# AudioMega_HaGeHa_DIL_v101.net
KiCad netlist of a schematic drawn in EAGLE
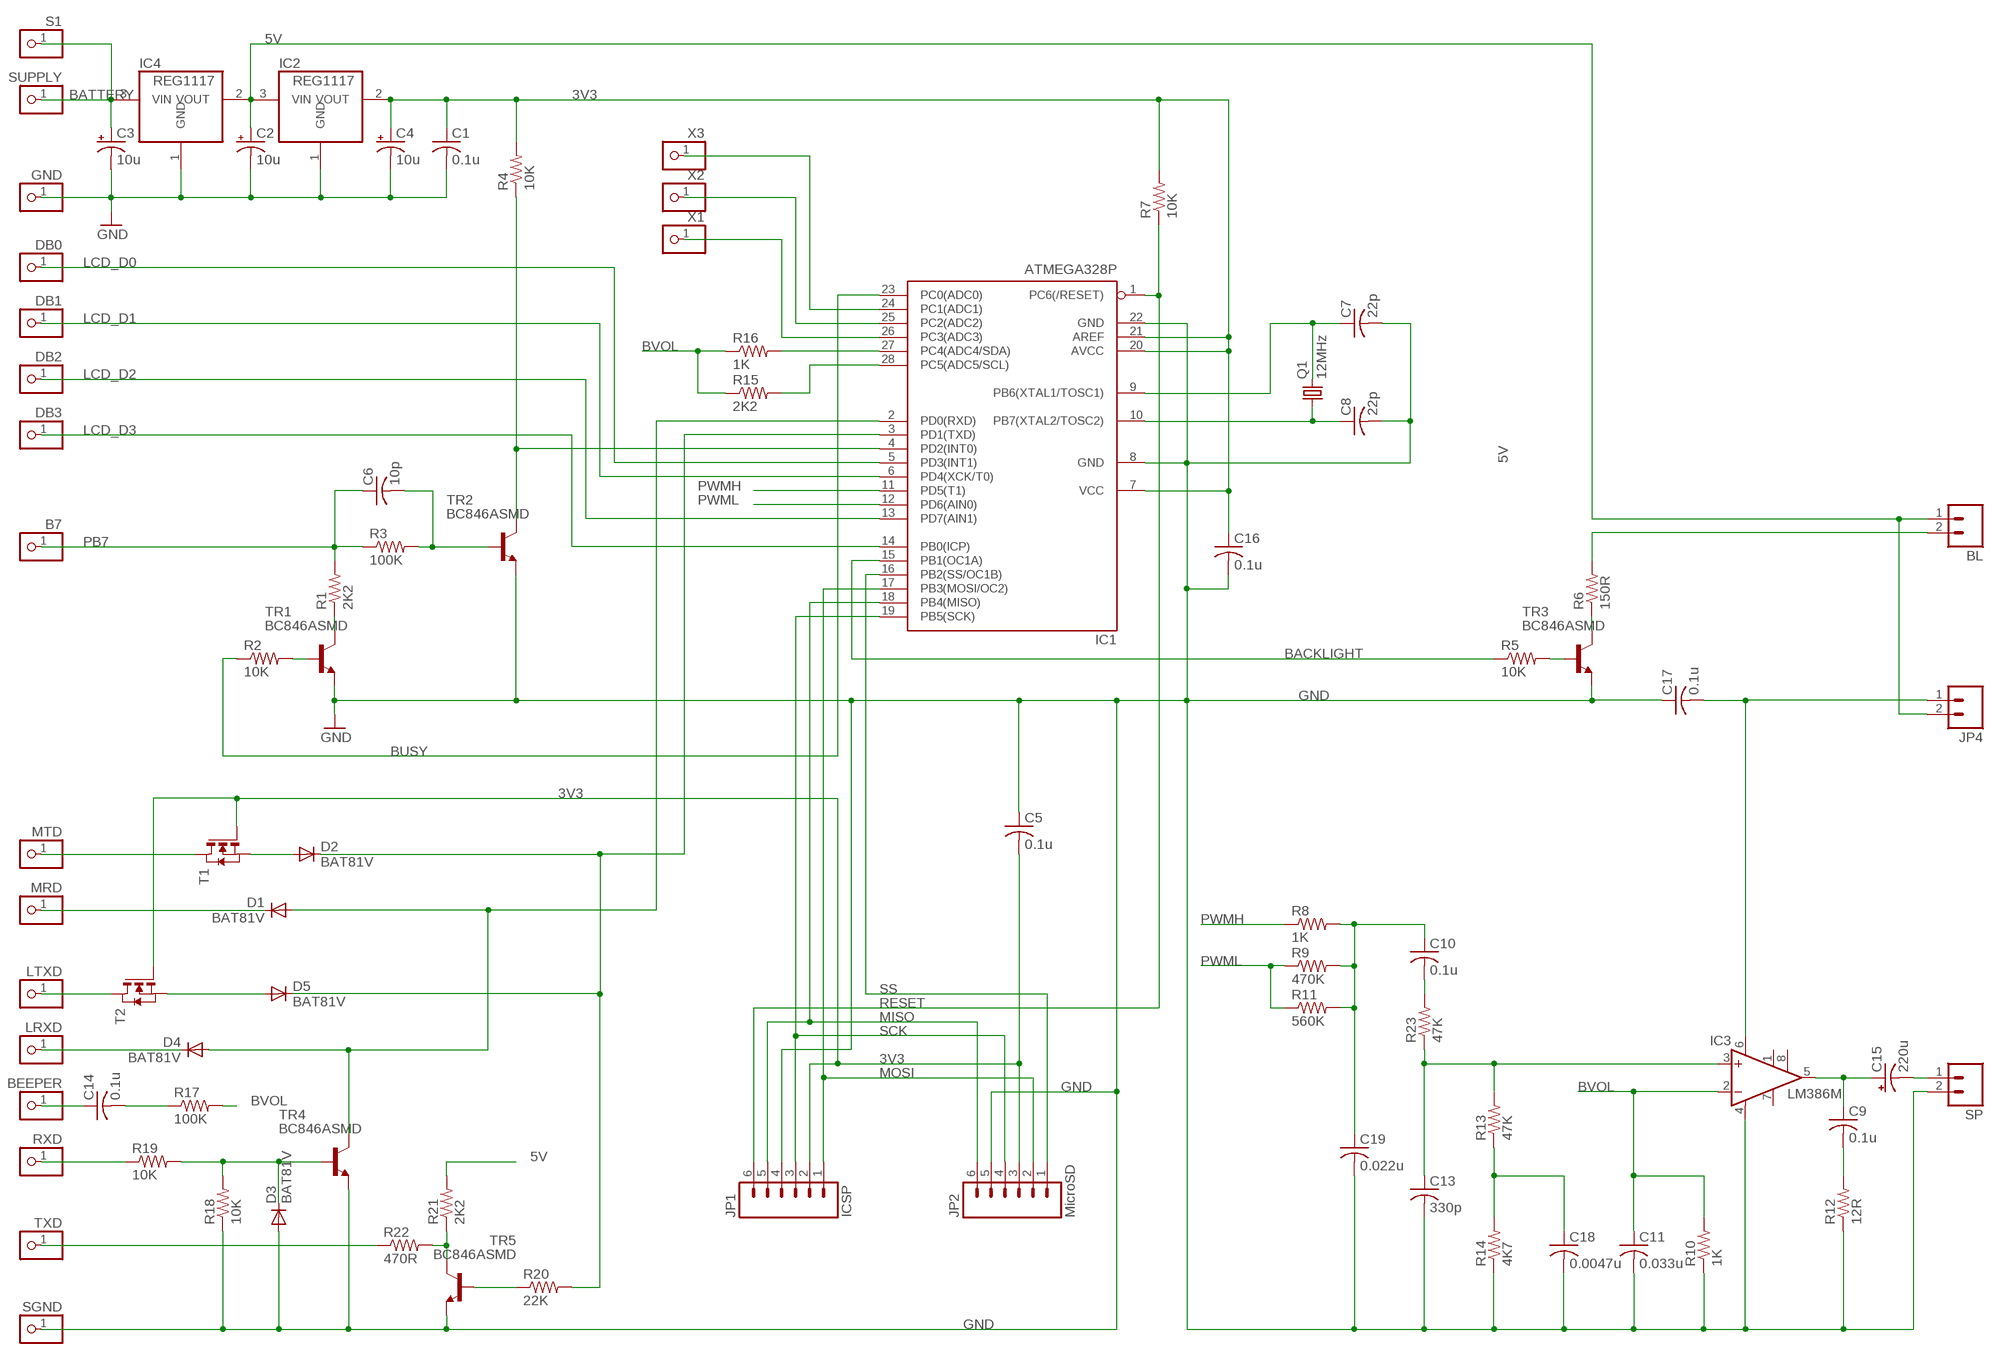
[diagram p0: schematic, sheet 1]

(export (version "E")
  (design (tool "Eeschema 10.0.6"))
  (components
    (comp (ref "B7")
      (value "PINHD-1X1")
      (footprint "eagle-import:1X01")
      (libsource (lib "eagle-import") (part "PINHD-1X1"))
    )
    (comp (ref "BEEPER")
      (value "PINHD-1X1")
      (footprint "eagle-import:1X01")
      (libsource (lib "eagle-import") (part "PINHD-1X1"))
    )
    (comp (ref "BL")
      (value "M02PTH")
      (footprint "eagle-import:1X02")
      (libsource (lib "eagle-import") (part "M02PTH"))
    )
    (comp (ref "C1")
      (value "0.1u")
      (footprint "eagle-import:C1206")
      (libsource (lib "eagle-import") (part "C-USC1206"))
    )
    (comp (ref "C2")
      (value "10u")
      (footprint "eagle-import:A_3216-18R")
      (libsource (lib "eagle-import") (part "CPOL-USA/3216-18R"))
    )
    (comp (ref "C3")
      (value "10u")
      (footprint "eagle-import:A_3216-18R")
      (libsource (lib "eagle-import") (part "CPOL-USA/3216-18R"))
    )
    (comp (ref "C4")
      (value "10u")
      (footprint "eagle-import:A_3216-18R")
      (libsource (lib "eagle-import") (part "CPOL-USA/3216-18R"))
    )
    (comp (ref "C5")
      (value "0.1u")
      (footprint "eagle-import:C1206")
      (libsource (lib "eagle-import") (part "C-USC1206"))
    )
    (comp (ref "C6")
      (value "10p")
      (footprint "eagle-import:C1206")
      (libsource (lib "eagle-import") (part "C-USC1206"))
    )
    (comp (ref "C7")
      (value "22p")
      (footprint "eagle-import:C1206")
      (libsource (lib "eagle-import") (part "C-USC1206"))
    )
    (comp (ref "C8")
      (value "22p")
      (footprint "eagle-import:C1206")
      (libsource (lib "eagle-import") (part "C-USC1206"))
    )
    (comp (ref "C9")
      (value "0.1u")
      (footprint "eagle-import:C1206")
      (libsource (lib "eagle-import") (part "C-USC1206"))
    )
    (comp (ref "C10")
      (value "0.1u")
      (footprint "eagle-import:C1206")
      (libsource (lib "eagle-import") (part "C-USC1206"))
    )
    (comp (ref "C11")
      (value "0.033u")
      (footprint "eagle-import:C1206")
      (libsource (lib "eagle-import") (part "C-USC1206"))
    )
    (comp (ref "C13")
      (value "330p")
      (footprint "eagle-import:C1206")
      (libsource (lib "eagle-import") (part "C-USC1206"))
    )
    (comp (ref "C14")
      (value "0.1u")
      (footprint "eagle-import:C1206")
      (libsource (lib "eagle-import") (part "C-USC1206"))
    )
    (comp (ref "C15")
      (value "220u")
      (footprint "eagle-import:CT7343")
      (libsource (lib "eagle-import") (part "CPOL-USCT7343"))
    )
    (comp (ref "C16")
      (value "0.1u")
      (footprint "eagle-import:C1206")
      (libsource (lib "eagle-import") (part "C-USC1206"))
    )
    (comp (ref "C17")
      (value "0.1u")
      (footprint "eagle-import:C1206")
      (libsource (lib "eagle-import") (part "C-USC1206"))
    )
    (comp (ref "C18")
      (value "0.0047u")
      (footprint "eagle-import:C1206")
      (libsource (lib "eagle-import") (part "C-USC1206"))
    )
    (comp (ref "C19")
      (value "0.022u")
      (footprint "eagle-import:C1206")
      (libsource (lib "eagle-import") (part "C-USC1206"))
    )
    (comp (ref "D1")
      (value "BAT81V")
      (footprint "eagle-import:SOD123")
      (libsource (lib "eagle-import") (part "DIODE-SOD123"))
    )
    (comp (ref "D2")
      (value "BAT81V")
      (footprint "eagle-import:SOD123")
      (libsource (lib "eagle-import") (part "DIODE-SOD123"))
    )
    (comp (ref "D3")
      (value "BAT81V")
      (footprint "eagle-import:SOD123")
      (libsource (lib "eagle-import") (part "DIODE-SOD123"))
    )
    (comp (ref "D4")
      (value "BAT81V")
      (footprint "eagle-import:SOD123")
      (libsource (lib "eagle-import") (part "DIODE-SOD123"))
    )
    (comp (ref "D5")
      (value "BAT81V")
      (footprint "eagle-import:SOD123")
      (libsource (lib "eagle-import") (part "DIODE-SOD123"))
    )
    (comp (ref "DB0")
      (value "PINHD-1X1")
      (footprint "eagle-import:1X01")
      (libsource (lib "eagle-import") (part "PINHD-1X1"))
    )
    (comp (ref "DB1")
      (value "PINHD-1X1")
      (footprint "eagle-import:1X01")
      (libsource (lib "eagle-import") (part "PINHD-1X1"))
    )
    (comp (ref "DB2")
      (value "PINHD-1X1")
      (footprint "eagle-import:1X01")
      (libsource (lib "eagle-import") (part "PINHD-1X1"))
    )
    (comp (ref "DB3")
      (value "PINHD-1X1")
      (footprint "eagle-import:1X01")
      (libsource (lib "eagle-import") (part "PINHD-1X1"))
    )
    (comp (ref "GND")
      (value "PINHD-1X1")
      (footprint "eagle-import:1X01")
      (libsource (lib "eagle-import") (part "PINHD-1X1"))
    )
    (comp (ref "IC1")
      (value "ATMEGA328P")
      (footprint "eagle-import:DIL28-3")
      (fields (field (name "OC_FARNELL") "unknown") (field (name "OC_NEWARK") "unknown"))
      (libsource (lib "eagle-import") (part "MEGA8-P"))
    )
    (comp (ref "IC2")
      (value "REG1117")
      (footprint "eagle-import:SOT223")
      (fields
        (field (name "MPN") "REG1117")
        (field (name "OC_FARNELL") "1097566")
        (field (name "OC_NEWARK") "14P6981")
      )
      (libsource (lib "eagle-import") (part "REG1117"))
    )
    (comp (ref "IC3")
      (value "LM386M")
      (footprint "eagle-import:DIL08")
      (libsource (lib "eagle-import") (part "LM386?-N1"))
    )
    (comp (ref "IC4")
      (value "REG1117")
      (footprint "eagle-import:SOT223")
      (libsource (lib "eagle-import") (part "REG1117"))
    )
    (comp (ref "JP1")
      (value "ICSP")
      (footprint "eagle-import:1X06")
      (libsource (lib "eagle-import") (part "M06SIP"))
    )
    (comp (ref "JP2")
      (value "MicroSD")
      (footprint "eagle-import:1X06")
      (libsource (lib "eagle-import") (part "M06SIP"))
    )
    (comp (ref "JP4")
      (value "M02PTH")
      (footprint "eagle-import:1X02")
      (libsource (lib "eagle-import") (part "M02PTH"))
    )
    (comp (ref "LRXD")
      (value "PINHD-1X1")
      (footprint "eagle-import:1X01")
      (libsource (lib "eagle-import") (part "PINHD-1X1"))
    )
    (comp (ref "LTXD")
      (value "PINHD-1X1")
      (footprint "eagle-import:1X01")
      (libsource (lib "eagle-import") (part "PINHD-1X1"))
    )
    (comp (ref "MRD")
      (value "PINHD-1X1")
      (footprint "eagle-import:1X01")
      (libsource (lib "eagle-import") (part "PINHD-1X1"))
    )
    (comp (ref "MTD")
      (value "PINHD-1X1")
      (footprint "eagle-import:1X01")
      (libsource (lib "eagle-import") (part "PINHD-1X1"))
    )
    (comp (ref "Q1")
      (value "12MHz")
      (footprint "eagle-import:HC49US")
      (libsource (lib "eagle-import") (part "CRYSTALHC49US"))
    )
    (comp (ref "R1")
      (value "2K2")
      (footprint "eagle-import:R1206")
      (libsource (lib "eagle-import") (part "R-US_R1206"))
    )
    (comp (ref "R2")
      (value "10K")
      (footprint "eagle-import:R1206")
      (libsource (lib "eagle-import") (part "R-US_R1206"))
    )
    (comp (ref "R3")
      (value "100K")
      (footprint "eagle-import:R1206")
      (libsource (lib "eagle-import") (part "R-US_R1206"))
    )
    (comp (ref "R4")
      (value "10K")
      (footprint "eagle-import:R1206")
      (libsource (lib "eagle-import") (part "R-US_R1206"))
    )
    (comp (ref "R5")
      (value "10K")
      (footprint "eagle-import:R1206")
      (libsource (lib "eagle-import") (part "R-US_R1206"))
    )
    (comp (ref "R6")
      (value "150R")
      (footprint "eagle-import:R1206")
      (libsource (lib "eagle-import") (part "R-US_R1206"))
    )
    (comp (ref "R7")
      (value "10K")
      (footprint "eagle-import:R1206")
      (libsource (lib "eagle-import") (part "R-US_R1206"))
    )
    (comp (ref "R8")
      (value "1K")
      (footprint "eagle-import:R1206")
      (libsource (lib "eagle-import") (part "R-US_R1206"))
    )
    (comp (ref "R9")
      (value "470K")
      (footprint "eagle-import:R1206")
      (libsource (lib "eagle-import") (part "R-US_R1206"))
    )
    (comp (ref "R10")
      (value "1K")
      (footprint "eagle-import:R1206")
      (libsource (lib "eagle-import") (part "R-US_R1206"))
    )
    (comp (ref "R11")
      (value "560K")
      (footprint "eagle-import:R1206")
      (libsource (lib "eagle-import") (part "R-US_R1206"))
    )
    (comp (ref "R12")
      (value "12R")
      (footprint "eagle-import:R1206")
      (libsource (lib "eagle-import") (part "R-US_R1206"))
    )
    (comp (ref "R13")
      (value "47K")
      (footprint "eagle-import:R1206")
      (libsource (lib "eagle-import") (part "R-US_R1206"))
    )
    (comp (ref "R14")
      (value "4K7")
      (footprint "eagle-import:R1206")
      (libsource (lib "eagle-import") (part "R-US_R1206"))
    )
    (comp (ref "R15")
      (value "2K2")
      (footprint "eagle-import:R1206")
      (libsource (lib "eagle-import") (part "R-US_R1206"))
    )
    (comp (ref "R16")
      (value "1K")
      (footprint "eagle-import:R1206")
      (libsource (lib "eagle-import") (part "R-US_R1206"))
    )
    (comp (ref "R17")
      (value "100K")
      (footprint "eagle-import:R1206")
      (libsource (lib "eagle-import") (part "R-US_R1206"))
    )
    (comp (ref "R18")
      (value "10K")
      (footprint "eagle-import:R1206")
      (libsource (lib "eagle-import") (part "R-US_R1206"))
    )
    (comp (ref "R19")
      (value "10K")
      (footprint "eagle-import:R1206")
      (libsource (lib "eagle-import") (part "R-US_R1206"))
    )
    (comp (ref "R20")
      (value "22K")
      (footprint "eagle-import:R1206")
      (libsource (lib "eagle-import") (part "R-US_R1206"))
    )
    (comp (ref "R21")
      (value "2K2")
      (footprint "eagle-import:R1206")
      (libsource (lib "eagle-import") (part "R-US_R1206"))
    )
    (comp (ref "R22")
      (value "470R")
      (footprint "eagle-import:R1206")
      (libsource (lib "eagle-import") (part "R-US_R1206"))
    )
    (comp (ref "R23")
      (value "47K")
      (footprint "eagle-import:R1206")
      (libsource (lib "eagle-import") (part "R-US_R1206"))
    )
    (comp (ref "RXD")
      (value "PINHD-1X1")
      (footprint "eagle-import:1X01")
      (libsource (lib "eagle-import") (part "PINHD-1X1"))
    )
    (comp (ref "S1")
      (value "PINHD-1X1")
      (footprint "eagle-import:1X01")
      (libsource (lib "eagle-import") (part "PINHD-1X1"))
    )
    (comp (ref "SGND")
      (value "PINHD-1X1")
      (footprint "eagle-import:1X01")
      (libsource (lib "eagle-import") (part "PINHD-1X1"))
    )
    (comp (ref "SP")
      (value "M02PTH")
      (footprint "eagle-import:1X02")
      (libsource (lib "eagle-import") (part "M02PTH"))
    )
    (comp (ref "SUPPLY")
      (value "PINHD-1X1")
      (footprint "eagle-import:1X01")
      (libsource (lib "eagle-import") (part "PINHD-1X1"))
    )
    (comp (ref "T1")
      (value "NMOSSOT23")
      (footprint "eagle-import:SOT-23")
      (libsource (lib "eagle-import") (part "NMOSSOT23"))
    )
    (comp (ref "T2")
      (value "NMOSSOT23")
      (footprint "eagle-import:SOT-23")
      (libsource (lib "eagle-import") (part "NMOSSOT23"))
    )
    (comp (ref "TR1")
      (value "BC846ASMD")
      (footprint "eagle-import:SOT23")
      (libsource (lib "eagle-import") (part "BC846SMDA"))
    )
    (comp (ref "TR2")
      (value "BC846ASMD")
      (footprint "eagle-import:SOT23")
      (libsource (lib "eagle-import") (part "BC846SMDA"))
    )
    (comp (ref "TR3")
      (value "BC846ASMD")
      (footprint "eagle-import:SOT23")
      (libsource (lib "eagle-import") (part "BC846SMDA"))
    )
    (comp (ref "TR4")
      (value "BC846ASMD")
      (footprint "eagle-import:SOT23")
      (libsource (lib "eagle-import") (part "BC846SMDA"))
    )
    (comp (ref "TR5")
      (value "BC846ASMD")
      (footprint "eagle-import:SOT23")
      (libsource (lib "eagle-import") (part "BC846SMDA"))
    )
    (comp (ref "TXD")
      (value "PINHD-1X1")
      (footprint "eagle-import:1X01")
      (libsource (lib "eagle-import") (part "PINHD-1X1"))
    )
    (comp (ref "X1")
      (value "PINHD-1X1")
      (footprint "eagle-import:1X01")
      (libsource (lib "eagle-import") (part "PINHD-1X1"))
    )
    (comp (ref "X2")
      (value "PINHD-1X1")
      (footprint "eagle-import:1X01")
      (libsource (lib "eagle-import") (part "PINHD-1X1"))
    )
    (comp (ref "X3")
      (value "PINHD-1X1")
      (footprint "eagle-import:1X01")
      (libsource (lib "eagle-import") (part "PINHD-1X1"))
    )
  )
  (nets
    (net (code "1") (name "/3V3") (class "Default")
      (node (ref "C1") (pin "1") (pinfunction "1_1") (pintype "passive"))
      (node (ref "C16") (pin "1") (pinfunction "1_1") (pintype "passive"))
      (node (ref "C4") (pin "+") (pinfunction "+_+") (pintype "passive"))
      (node (ref "C5") (pin "2") (pinfunction "2_2") (pintype "passive"))
      (node (ref "IC1") (pin "20") (pinfunction "AVCC_20") (pintype "power_in"))
      (node (ref "IC1") (pin "21") (pinfunction "AREF_21") (pintype "passive"))
      (node (ref "IC1") (pin "7") (pinfunction "VCC_7") (pintype "power_in"))
      (node (ref "IC2") (pin "2") (pinfunction "VOUT_2") (pintype "output"))
      (node (ref "JP1") (pin "2") (pinfunction "2_2") (pintype "passive"))
      (node (ref "JP2") (pin "3") (pinfunction "3_3") (pintype "passive"))
      (node (ref "R4") (pin "2") (pinfunction "2_2") (pintype "passive"))
      (node (ref "R7") (pin "2") (pinfunction "2_2") (pintype "passive"))
      (node (ref "T1") (pin "3") (pinfunction "G_3") (pintype "passive"))
      (node (ref "T2") (pin "3") (pinfunction "G_3") (pintype "passive"))
    )
    (net (code "2") (name "/5V") (class "Default")
      (node (ref "BL") (pin "1") (pinfunction "1_1") (pintype "passive"))
      (node (ref "C2") (pin "+") (pinfunction "+_+") (pintype "passive"))
      (node (ref "IC2") (pin "3") (pinfunction "VIN_3") (pintype "input"))
      (node (ref "IC4") (pin "2") (pinfunction "VOUT_2") (pintype "output"))
      (node (ref "JP4") (pin "2") (pinfunction "2_2") (pintype "passive"))
      (node (ref "R21") (pin "2") (pinfunction "2_2") (pintype "passive"))
    )
    (net (code "3") (name "/BACKLIGHT") (class "Default")
      (node (ref "IC1") (pin "15") (pinfunction "PB1(OC1A)_15") (pintype "bidirectional"))
      (node (ref "R5") (pin "1") (pinfunction "1_1") (pintype "passive"))
    )
    (net (code "4") (name "/BATTERY") (class "Default")
      (node (ref "C3") (pin "+") (pinfunction "+_+") (pintype "passive"))
      (node (ref "IC4") (pin "3") (pinfunction "VIN_3") (pintype "input"))
      (node (ref "S1") (pin "1") (pinfunction "1_1") (pintype "passive"))
      (node (ref "SUPPLY") (pin "1") (pinfunction "1_1") (pintype "passive"))
    )
    (net (code "5") (name "/BUSY") (class "Default")
      (node (ref "IC1") (pin "23") (pinfunction "PC0(ADC0)_23") (pintype "bidirectional"))
      (node (ref "R2") (pin "1") (pinfunction "1_1") (pintype "passive"))
    )
    (net (code "6") (name "/BVOL") (class "Default")
      (node (ref "C11") (pin "1") (pinfunction "1_1") (pintype "passive"))
      (node (ref "IC3") (pin "2") (pinfunction "-IN_2") (pintype "input"))
      (node (ref "R10") (pin "2") (pinfunction "2_2") (pintype "passive"))
      (node (ref "R15") (pin "1") (pinfunction "1_1") (pintype "passive"))
      (node (ref "R16") (pin "1") (pinfunction "1_1") (pintype "passive"))
      (node (ref "R17") (pin "2") (pinfunction "2_2") (pintype "passive"))
    )
    (net (code "7") (name "/LCD_D0") (class "Default")
      (node (ref "DB0") (pin "1") (pinfunction "1_1") (pintype "passive"))
      (node (ref "IC1") (pin "5") (pinfunction "PD3(INT1)_5") (pintype "bidirectional"))
    )
    (net (code "8") (name "/LCD_D1") (class "Default")
      (node (ref "DB1") (pin "1") (pinfunction "1_1") (pintype "passive"))
      (node (ref "IC1") (pin "6") (pinfunction "PD4(XCK/T0)_6") (pintype "bidirectional"))
    )
    (net (code "9") (name "/LCD_D2") (class "Default")
      (node (ref "DB2") (pin "1") (pinfunction "1_1") (pintype "passive"))
      (node (ref "IC1") (pin "13") (pinfunction "PD7(AIN1)_13") (pintype "bidirectional"))
    )
    (net (code "10") (name "/LCD_D3") (class "Default")
      (node (ref "DB3") (pin "1") (pinfunction "1_1") (pintype "passive"))
      (node (ref "IC1") (pin "14") (pinfunction "PB0(ICP)_14") (pintype "bidirectional"))
    )
    (net (code "11") (name "/MISO") (class "Default")
      (node (ref "IC1") (pin "18") (pinfunction "PB4(MISO)_18") (pintype "bidirectional"))
      (node (ref "JP1") (pin "5") (pinfunction "5_5") (pintype "passive"))
      (node (ref "JP2") (pin "6") (pinfunction "6_6") (pintype "passive"))
    )
    (net (code "12") (name "/MOSI") (class "Default")
      (node (ref "IC1") (pin "17") (pinfunction "PB3(MOSI/OC2)_17") (pintype "bidirectional"))
      (node (ref "JP1") (pin "1") (pinfunction "1_1") (pintype "passive"))
      (node (ref "JP2") (pin "2") (pinfunction "2_2") (pintype "passive"))
    )
    (net (code "13") (name "/PB7") (class "Default")
      (node (ref "B7") (pin "1") (pinfunction "1_1") (pintype "passive"))
      (node (ref "C6") (pin "1") (pinfunction "1_1") (pintype "passive"))
      (node (ref "R1") (pin "2") (pinfunction "2_2") (pintype "passive"))
      (node (ref "R3") (pin "1") (pinfunction "1_1") (pintype "passive"))
    )
    (net (code "14") (name "/PWMH") (class "Default")
      (node (ref "IC1") (pin "11") (pinfunction "PD5(T1)_11") (pintype "bidirectional"))
      (node (ref "R8") (pin "1") (pinfunction "1_1") (pintype "passive"))
    )
    (net (code "15") (name "/PWML") (class "Default")
      (node (ref "IC1") (pin "12") (pinfunction "PD6(AIN0)_12") (pintype "bidirectional"))
      (node (ref "R11") (pin "1") (pinfunction "1_1") (pintype "passive"))
      (node (ref "R9") (pin "1") (pinfunction "1_1") (pintype "passive"))
    )
    (net (code "16") (name "/RESET") (class "Default")
      (node (ref "IC1") (pin "1") (pinfunction "PC6(/RESET)_1") (pintype "bidirectional"))
      (node (ref "JP1") (pin "6") (pinfunction "6_6") (pintype "passive"))
      (node (ref "R7") (pin "1") (pinfunction "1_1") (pintype "passive"))
    )
    (net (code "17") (name "/SCK") (class "Default")
      (node (ref "IC1") (pin "19") (pinfunction "PB5(SCK)_19") (pintype "bidirectional"))
      (node (ref "JP1") (pin "3") (pinfunction "3_3") (pintype "passive"))
      (node (ref "JP2") (pin "4") (pinfunction "4_4") (pintype "passive"))
    )
    (net (code "18") (name "/SS") (class "Default")
      (node (ref "IC1") (pin "16") (pinfunction "PB2(SS/OC1B)_16") (pintype "bidirectional"))
      (node (ref "JP2") (pin "1") (pinfunction "1_1") (pintype "passive"))
    )
    (net (code "19") (name "GND") (class "Default")
      (node (ref "C1") (pin "2") (pinfunction "2_2") (pintype "passive"))
      (node (ref "C11") (pin "2") (pinfunction "2_2") (pintype "passive"))
      (node (ref "C13") (pin "2") (pinfunction "2_2") (pintype "passive"))
      (node (ref "C16") (pin "2") (pinfunction "2_2") (pintype "passive"))
      (node (ref "C17") (pin "1") (pinfunction "1_1") (pintype "passive"))
      (node (ref "C18") (pin "2") (pinfunction "2_2") (pintype "passive"))
      (node (ref "C19") (pin "2") (pinfunction "2_2") (pintype "passive"))
      (node (ref "C2") (pin "-") (pinfunction "-_-") (pintype "passive"))
      (node (ref "C3") (pin "-") (pinfunction "-_-") (pintype "passive"))
      (node (ref "C4") (pin "-") (pinfunction "-_-") (pintype "passive"))
      (node (ref "C5") (pin "1") (pinfunction "1_1") (pintype "passive"))
      (node (ref "C7") (pin "2") (pinfunction "2_2") (pintype "passive"))
      (node (ref "C8") (pin "2") (pinfunction "2_2") (pintype "passive"))
      (node (ref "D3") (pin "A") (pinfunction "A_A") (pintype "passive"))
      (node (ref "GND") (pin "1") (pinfunction "1_1") (pintype "passive"))
      (node (ref "IC1") (pin "22") (pinfunction "GND_22") (pintype "power_in"))
      (node (ref "IC1") (pin "8") (pinfunction "GND_8") (pintype "power_in"))
      (node (ref "IC2") (pin "1") (pinfunction "GND_1") (pintype "power_in"))
      (node (ref "IC3") (pin "4") (pinfunction "GND_4") (pintype "power_in"))
      (node (ref "IC4") (pin "1") (pinfunction "GND_1") (pintype "power_in"))
      (node (ref "JP1") (pin "4") (pinfunction "4_4") (pintype "passive"))
      (node (ref "JP2") (pin "5") (pinfunction "5_5") (pintype "passive"))
      (node (ref "R10") (pin "1") (pinfunction "1_1") (pintype "passive"))
      (node (ref "R12") (pin "1") (pinfunction "1_1") (pintype "passive"))
      (node (ref "R14") (pin "1") (pinfunction "1_1") (pintype "passive"))
      (node (ref "R18") (pin "1") (pinfunction "1_1") (pintype "passive"))
      (node (ref "SGND") (pin "1") (pinfunction "1_1") (pintype "passive"))
      (node (ref "SP") (pin "2") (pinfunction "2_2") (pintype "passive"))
      (node (ref "TR1") (pin "2") (pinfunction "E_2") (pintype "passive"))
      (node (ref "TR2") (pin "2") (pinfunction "E_2") (pintype "passive"))
      (node (ref "TR3") (pin "2") (pinfunction "E_2") (pintype "passive"))
      (node (ref "TR4") (pin "2") (pinfunction "E_2") (pintype "passive"))
      (node (ref "TR5") (pin "2") (pinfunction "E_2") (pintype "passive"))
    )
    (net (code "20") (name "Net-(BEEPER-Pad1)") (class "Default")
      (node (ref "BEEPER") (pin "1") (pinfunction "1_1") (pintype "passive"))
      (node (ref "C14") (pin "1") (pinfunction "1_1") (pintype "passive"))
    )
    (net (code "21") (name "Net-(BL-Pad2)") (class "Default")
      (node (ref "BL") (pin "2") (pinfunction "2_2") (pintype "passive"))
      (node (ref "R6") (pin "2") (pinfunction "2_2") (pintype "passive"))
    )
    (net (code "22") (name "Net-(C9-Pad2)") (class "Default")
      (node (ref "C9") (pin "2") (pinfunction "2_2") (pintype "passive"))
      (node (ref "R12") (pin "2") (pinfunction "2_2") (pintype "passive"))
    )
    (net (code "23") (name "Net-(C10-Pad1)") (class "Default")
      (node (ref "C10") (pin "1") (pinfunction "1_1") (pintype "passive"))
      (node (ref "C19") (pin "1") (pinfunction "1_1") (pintype "passive"))
      (node (ref "R11") (pin "2") (pinfunction "2_2") (pintype "passive"))
      (node (ref "R8") (pin "2") (pinfunction "2_2") (pintype "passive"))
      (node (ref "R9") (pin "2") (pinfunction "2_2") (pintype "passive"))
    )
    (net (code "24") (name "Net-(C10-Pad2)") (class "Default")
      (node (ref "C10") (pin "2") (pinfunction "2_2") (pintype "passive"))
      (node (ref "R23") (pin "2") (pinfunction "2_2") (pintype "passive"))
    )
    (net (code "25") (name "Net-(C14-Pad2)") (class "Default")
      (node (ref "C14") (pin "2") (pinfunction "2_2") (pintype "passive"))
      (node (ref "R17") (pin "1") (pinfunction "1_1") (pintype "passive"))
    )
    (net (code "26") (name "Net-(C15-Pad-)") (class "Default")
      (node (ref "C15") (pin "-") (pinfunction "-_-") (pintype "passive"))
      (node (ref "SP") (pin "1") (pinfunction "1_1") (pintype "passive"))
    )
    (net (code "27") (name "Net-(C18-Pad1)") (class "Default")
      (node (ref "C18") (pin "1") (pinfunction "1_1") (pintype "passive"))
      (node (ref "R13") (pin "1") (pinfunction "1_1") (pintype "passive"))
      (node (ref "R14") (pin "2") (pinfunction "2_2") (pintype "passive"))
    )
    (net (code "28") (name "Net-(D1-PadC)") (class "Default")
      (node (ref "D1") (pin "C") (pinfunction "C_C") (pintype "passive"))
      (node (ref "MRD") (pin "1") (pinfunction "1_1") (pintype "passive"))
    )
    (net (code "29") (name "Net-(D4-PadC)") (class "Default")
      (node (ref "D4") (pin "C") (pinfunction "C_C") (pintype "passive"))
      (node (ref "LRXD") (pin "1") (pinfunction "1_1") (pintype "passive"))
    )
    (net (code "30") (name "Net-(IC1-PB6(XTAL1{slash}TOSC1))") (class "Default")
      (node (ref "C7") (pin "1") (pinfunction "1_1") (pintype "passive"))
      (node (ref "IC1") (pin "9") (pinfunction "PB6(XTAL1/TOSC1)_9") (pintype "bidirectional"))
      (node (ref "Q1") (pin "2") (pinfunction "2_2") (pintype "passive"))
    )
    (net (code "31") (name "Net-(IC1-PB7(XTAL2{slash}TOSC2))") (class "Default")
      (node (ref "C8") (pin "1") (pinfunction "1_1") (pintype "passive"))
      (node (ref "IC1") (pin "10") (pinfunction "PB7(XTAL2/TOSC2)_10") (pintype "bidirectional"))
      (node (ref "Q1") (pin "1") (pinfunction "1_1") (pintype "passive"))
    )
    (net (code "32") (name "Net-(IC1-PC1(ADC1))") (class "Default")
      (node (ref "IC1") (pin "24") (pinfunction "PC1(ADC1)_24") (pintype "bidirectional"))
      (node (ref "X3") (pin "1") (pinfunction "1_1") (pintype "passive"))
    )
    (net (code "33") (name "Net-(IC1-PC2(ADC2))") (class "Default")
      (node (ref "IC1") (pin "25") (pinfunction "PC2(ADC2)_25") (pintype "bidirectional"))
      (node (ref "X2") (pin "1") (pinfunction "1_1") (pintype "passive"))
    )
    (net (code "34") (name "Net-(IC1-PC3(ADC3))") (class "Default")
      (node (ref "IC1") (pin "26") (pinfunction "PC3(ADC3)_26") (pintype "bidirectional"))
      (node (ref "X1") (pin "1") (pinfunction "1_1") (pintype "passive"))
    )
    (net (code "35") (name "Net-(IC1-PC4(ADC4{slash}SDA))") (class "Default")
      (node (ref "IC1") (pin "27") (pinfunction "PC4(ADC4/SDA)_27") (pintype "bidirectional"))
      (node (ref "R16") (pin "2") (pinfunction "2_2") (pintype "passive"))
    )
    (net (code "36") (name "Net-(IC1-PC5(ADC5{slash}SCL))") (class "Default")
      (node (ref "IC1") (pin "28") (pinfunction "PC5(ADC5/SCL)_28") (pintype "bidirectional"))
      (node (ref "R15") (pin "2") (pinfunction "2_2") (pintype "passive"))
    )
    (net (code "37") (name "Net-(IC1-PD0(RXD))") (class "Default")
      (node (ref "D1") (pin "A") (pinfunction "A_A") (pintype "passive"))
      (node (ref "D4") (pin "A") (pinfunction "A_A") (pintype "passive"))
      (node (ref "IC1") (pin "2") (pinfunction "PD0(RXD)_2") (pintype "bidirectional"))
      (node (ref "TR4") (pin "3") (pinfunction "C_3") (pintype "passive"))
    )
    (net (code "38") (name "Net-(IC1-PD1(TXD))") (class "Default")
      (node (ref "D2") (pin "C") (pinfunction "C_C") (pintype "passive"))
      (node (ref "D5") (pin "C") (pinfunction "C_C") (pintype "passive"))
      (node (ref "IC1") (pin "3") (pinfunction "PD1(TXD)_3") (pintype "bidirectional"))
      (node (ref "R20") (pin "2") (pinfunction "2_2") (pintype "passive"))
    )
    (net (code "39") (name "Net-(IC1-PD2(INT0))") (class "Default")
      (node (ref "IC1") (pin "4") (pinfunction "PD2(INT0)_4") (pintype "bidirectional"))
      (node (ref "R4") (pin "1") (pinfunction "1_1") (pintype "passive"))
      (node (ref "TR2") (pin "3") (pinfunction "C_3") (pintype "passive"))
    )
    (net (code "40") (name "Net-(IC3-+IN)") (class "Default")
      (node (ref "C13") (pin "1") (pinfunction "1_1") (pintype "passive"))
      (node (ref "IC3") (pin "3") (pinfunction "+IN_3") (pintype "input"))
      (node (ref "R13") (pin "2") (pinfunction "2_2") (pintype "passive"))
      (node (ref "R23") (pin "1") (pinfunction "1_1") (pintype "passive"))
    )
    (net (code "41") (name "Net-(IC3-OUT)") (class "Default")
      (node (ref "C15") (pin "+") (pinfunction "+_+") (pintype "passive"))
      (node (ref "C9") (pin "1") (pinfunction "1_1") (pintype "passive"))
      (node (ref "IC3") (pin "5") (pinfunction "OUT_5") (pintype "output"))
    )
    (net (code "42") (name "Net-(IC3-VS)") (class "Default")
      (node (ref "C17") (pin "2") (pinfunction "2_2") (pintype "passive"))
      (node (ref "IC3") (pin "6") (pinfunction "VS_6") (pintype "power_in"))
      (node (ref "JP4") (pin "1") (pinfunction "1_1") (pintype "passive"))
    )
    (net (code "43") (name "Net-(R19-Pad1)") (class "Default")
      (node (ref "R19") (pin "1") (pinfunction "1_1") (pintype "passive"))
      (node (ref "RXD") (pin "1") (pinfunction "1_1") (pintype "passive"))
    )
    (net (code "44") (name "Net-(R22-Pad1)") (class "Default")
      (node (ref "R22") (pin "1") (pinfunction "1_1") (pintype "passive"))
      (node (ref "TXD") (pin "1") (pinfunction "1_1") (pintype "passive"))
    )
    (net (code "45") (name "Net-(T1-D)") (class "Default")
      (node (ref "MTD") (pin "1") (pinfunction "1_1") (pintype "passive"))
      (node (ref "T1") (pin "1") (pinfunction "D_1") (pintype "passive"))
    )
    (net (code "46") (name "Net-(T1-S)") (class "Default")
      (node (ref "D2") (pin "A") (pinfunction "A_A") (pintype "passive"))
      (node (ref "T1") (pin "2") (pinfunction "S_2") (pintype "passive"))
    )
    (net (code "47") (name "Net-(T2-D)") (class "Default")
      (node (ref "LTXD") (pin "1") (pinfunction "1_1") (pintype "passive"))
      (node (ref "T2") (pin "1") (pinfunction "D_1") (pintype "passive"))
    )
    (net (code "48") (name "Net-(T2-S)") (class "Default")
      (node (ref "D5") (pin "A") (pinfunction "A_A") (pintype "passive"))
      (node (ref "T2") (pin "2") (pinfunction "S_2") (pintype "passive"))
    )
    (net (code "49") (name "Net-(TR1-B)") (class "Default")
      (node (ref "R2") (pin "2") (pinfunction "2_2") (pintype "passive"))
      (node (ref "TR1") (pin "1") (pinfunction "B_1") (pintype "passive"))
    )
    (net (code "50") (name "Net-(TR1-C)") (class "Default")
      (node (ref "R1") (pin "1") (pinfunction "1_1") (pintype "passive"))
      (node (ref "TR1") (pin "3") (pinfunction "C_3") (pintype "passive"))
    )
    (net (code "51") (name "Net-(TR2-B)") (class "Default")
      (node (ref "C6") (pin "2") (pinfunction "2_2") (pintype "passive"))
      (node (ref "R3") (pin "2") (pinfunction "2_2") (pintype "passive"))
      (node (ref "TR2") (pin "1") (pinfunction "B_1") (pintype "passive"))
    )
    (net (code "52") (name "Net-(TR3-B)") (class "Default")
      (node (ref "R5") (pin "2") (pinfunction "2_2") (pintype "passive"))
      (node (ref "TR3") (pin "1") (pinfunction "B_1") (pintype "passive"))
    )
    (net (code "53") (name "Net-(TR3-C)") (class "Default")
      (node (ref "R6") (pin "1") (pinfunction "1_1") (pintype "passive"))
      (node (ref "TR3") (pin "3") (pinfunction "C_3") (pintype "passive"))
    )
    (net (code "54") (name "Net-(TR4-B)") (class "Default")
      (node (ref "D3") (pin "C") (pinfunction "C_C") (pintype "passive"))
      (node (ref "R18") (pin "2") (pinfunction "2_2") (pintype "passive"))
      (node (ref "R19") (pin "2") (pinfunction "2_2") (pintype "passive"))
      (node (ref "TR4") (pin "1") (pinfunction "B_1") (pintype "passive"))
    )
    (net (code "55") (name "Net-(TR5-B)") (class "Default")
      (node (ref "R20") (pin "1") (pinfunction "1_1") (pintype "passive"))
      (node (ref "TR5") (pin "1") (pinfunction "B_1") (pintype "passive"))
    )
    (net (code "56") (name "Net-(TR5-C)") (class "Default")
      (node (ref "R21") (pin "1") (pinfunction "1_1") (pintype "passive"))
      (node (ref "R22") (pin "2") (pinfunction "2_2") (pintype "passive"))
      (node (ref "TR5") (pin "3") (pinfunction "C_3") (pintype "passive"))
    )
    (net (code "57") (name "unconnected-(IC3-BYPASS-Pad7)") (class "Default")
      (node (ref "IC3") (pin "7") (pinfunction "BYPASS_7") (pintype "passive"))
    )
    (net (code "58") (name "unconnected-(IC3-GAIN-Pad1)") (class "Default")
      (node (ref "IC3") (pin "1") (pinfunction "GAIN_1") (pintype "passive"))
    )
    (net (code "59") (name "unconnected-(IC3-GAIN-Pad8)") (class "Default")
      (node (ref "IC3") (pin "8") (pinfunction "GAIN_8") (pintype "passive"))
    )
  )
)
